# CameraTrigger.net
KiCad netlist of a schematic drawn in EAGLE
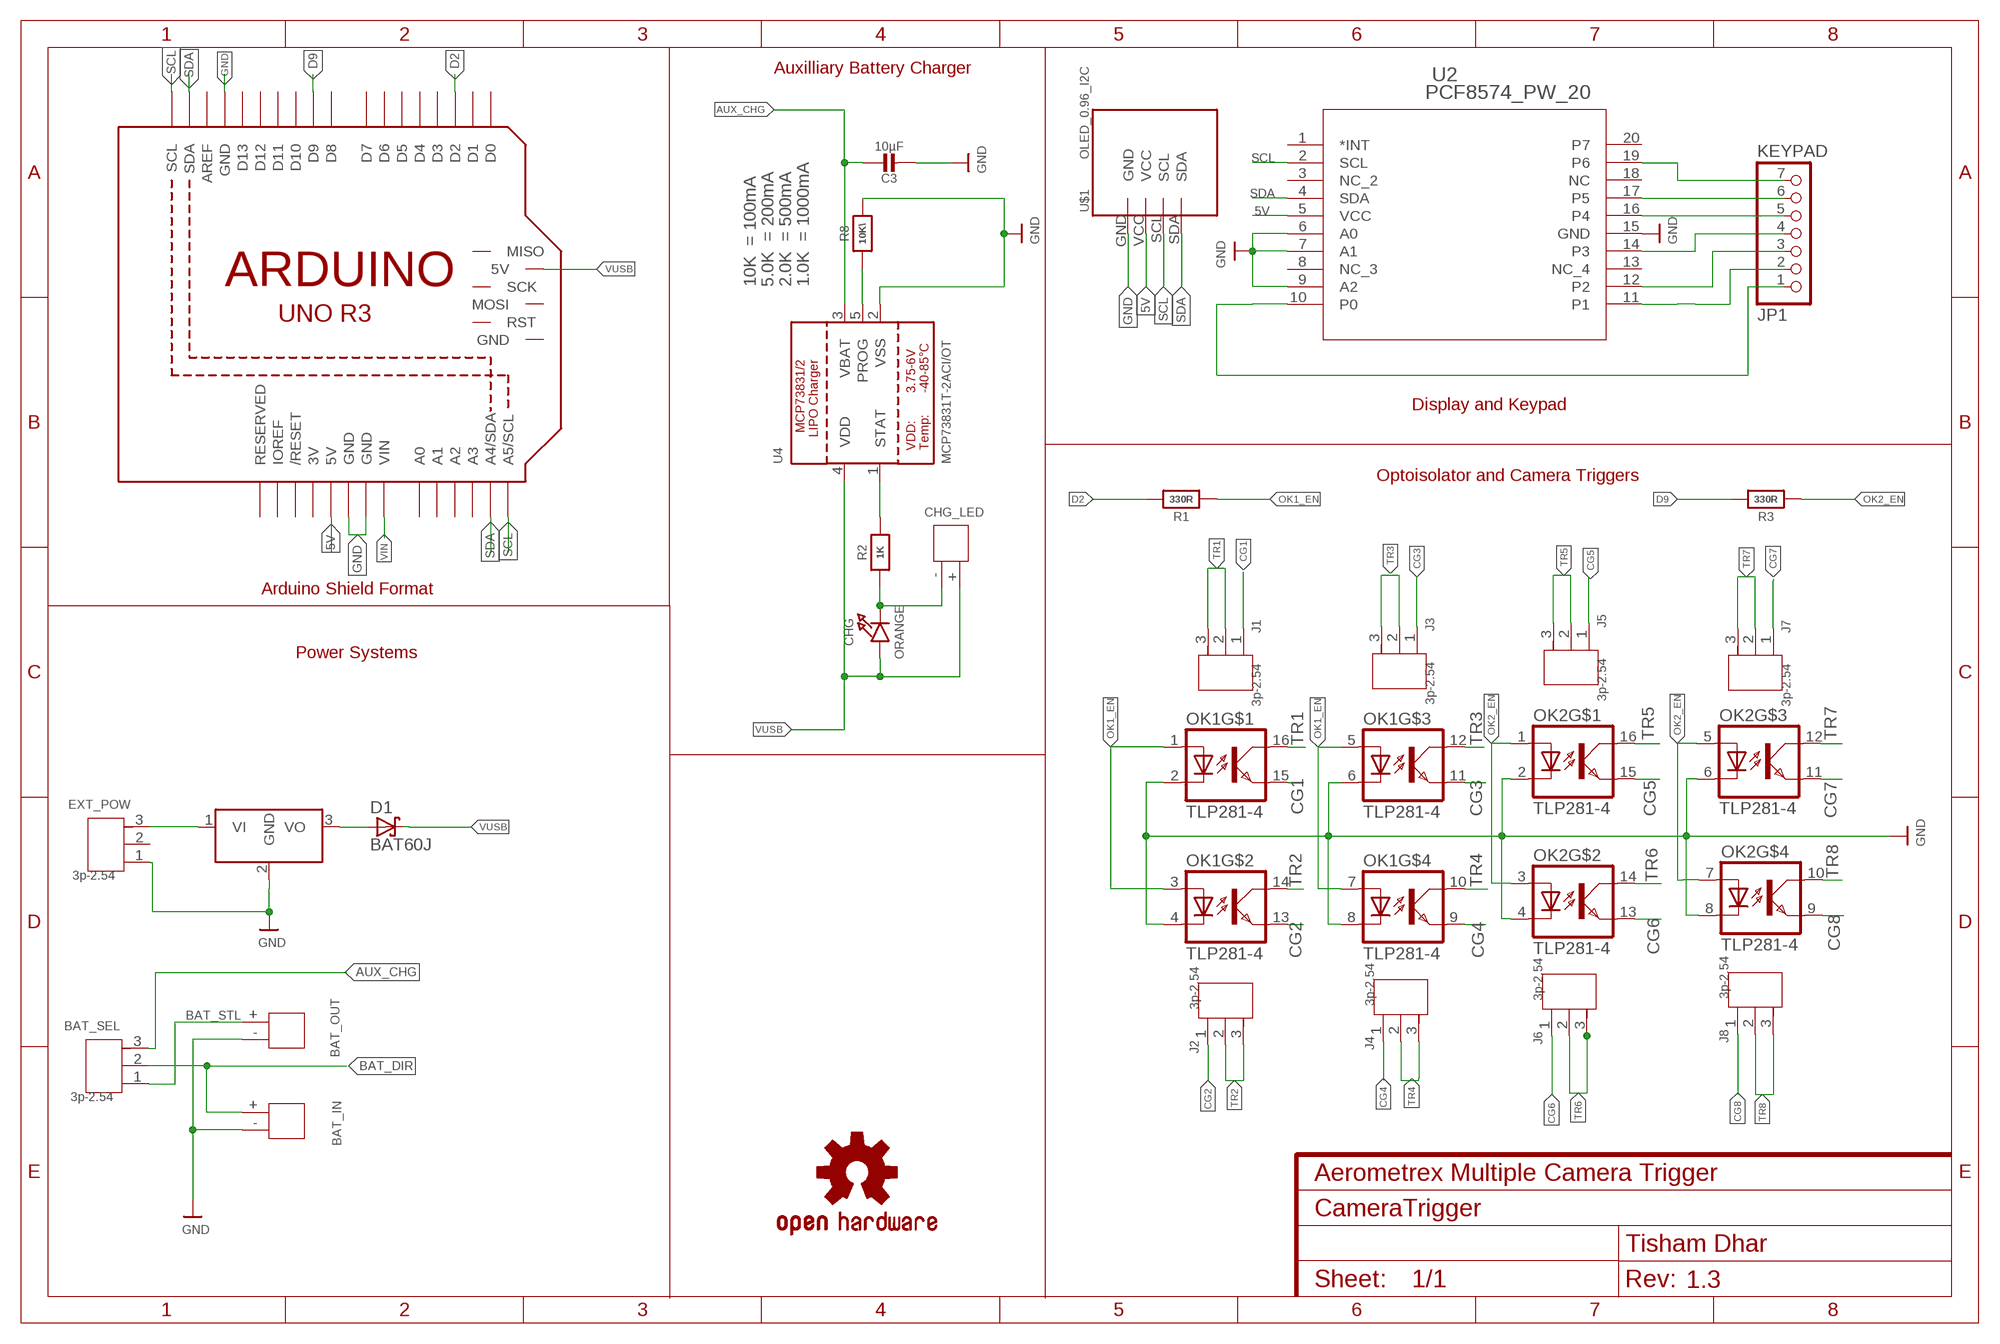
[diagram p0: schematic, sheet 1]

(export (version "E")
  (design (tool "Eeschema 10.0.6"))
  (components
    (comp (ref "BAT_IN")
      (value "2p-2.0")
      (footprint "eagle-import:H2-2.0-6X4.5MM")
      (libsource (lib "eagle-import") (part "DIP-JST-2P-2.0"))
    )
    (comp (ref "BAT_OUT")
      (value "2p-2.0")
      (footprint "eagle-import:H2-2.0-6X4.5MM")
      (libsource (lib "eagle-import") (part "DIP-JST-2P-2.0"))
    )
    (comp (ref "BAT_SEL")
      (value "3p-2.54")
      (footprint "eagle-import:HW3-2.54-7.62X6.6MM")
      (fields (field (name "MPN") "B101-103A0BSBA1"))
      (libsource (lib "eagle-import") (part "DIP-FEMALE-JST(3P-2.54)"))
    )
    (comp (ref "C3")
      (value "10µF")
      (footprint "eagle-import:0805-NO")
      (libsource (lib "eagle-import") (part "CAP_CERAMIC0805-NOOUTLINE"))
    )
    (comp (ref "CHG")
      (value "ORANGE")
      (footprint "eagle-import:CHIPLED_0805_NOOUTLINE")
      (libsource (lib "eagle-import") (part "LED0805_NOOUTLINE"))
    )
    (comp (ref "CHG_LED")
      (value "2p-2.0")
      (footprint "eagle-import:H2-2.0-6X4.5MM")
      (libsource (lib "eagle-import") (part "DIP-JST-2P-2.0"))
    )
    (comp (ref "D1")
      (value "BAT60J")
      (footprint "eagle-import:SOD323_ST")
      (libsource (lib "eagle-import") (part "BAT60J"))
    )
    (comp (ref "EXT_POW")
      (value "3p-2.54")
      (footprint "eagle-import:HW3-2.54-7.62X6.6MM")
      (fields (field (name "MPN") "B101-103A0BSBA1"))
      (libsource (lib "eagle-import") (part "DIP-FEMALE-JST(3P-2.54)"))
    )
    (comp (ref "J1")
      (value "3p-2.54")
      (footprint "eagle-import:HW3-2.54-7.62X6.6MM")
      (fields (field (name "MPN") "B101-103A0BSBA1"))
      (libsource (lib "eagle-import") (part "DIP-FEMALE-JST(3P-2.54)"))
    )
    (comp (ref "J2")
      (value "3p-2.54")
      (footprint "eagle-import:HW3-2.54-7.62X6.6MM")
      (fields (field (name "MPN") "B101-103A0BSBA1"))
      (libsource (lib "eagle-import") (part "DIP-FEMALE-JST(3P-2.54)"))
    )
    (comp (ref "J3")
      (value "3p-2.54")
      (footprint "eagle-import:HW3-2.54-7.62X6.6MM")
      (fields (field (name "MPN") "B101-103A0BSBA1"))
      (libsource (lib "eagle-import") (part "DIP-FEMALE-JST(3P-2.54)"))
    )
    (comp (ref "J4")
      (value "3p-2.54")
      (footprint "eagle-import:HW3-2.54-7.62X6.6MM")
      (fields (field (name "MPN") "B101-103A0BSBA1"))
      (libsource (lib "eagle-import") (part "DIP-FEMALE-JST(3P-2.54)"))
    )
    (comp (ref "J5")
      (value "3p-2.54")
      (footprint "eagle-import:HW3-2.54-7.62X6.6MM")
      (fields (field (name "MPN") "B101-103A0BSBA1"))
      (libsource (lib "eagle-import") (part "DIP-FEMALE-JST(3P-2.54)"))
    )
    (comp (ref "J6")
      (value "3p-2.54")
      (footprint "eagle-import:HW3-2.54-7.62X6.6MM")
      (fields (field (name "MPN") "B101-103A0BSBA1"))
      (libsource (lib "eagle-import") (part "DIP-FEMALE-JST(3P-2.54)"))
    )
    (comp (ref "J7")
      (value "3p-2.54")
      (footprint "eagle-import:HW3-2.54-7.62X6.6MM")
      (fields (field (name "MPN") "B101-103A0BSBA1"))
      (libsource (lib "eagle-import") (part "DIP-FEMALE-JST(3P-2.54)"))
    )
    (comp (ref "J8")
      (value "3p-2.54")
      (footprint "eagle-import:HW3-2.54-7.62X6.6MM")
      (fields (field (name "MPN") "B101-103A0BSBA1"))
      (libsource (lib "eagle-import") (part "DIP-FEMALE-JST(3P-2.54)"))
    )
    (comp (ref "JP1")
      (value "KEYPAD")
      (footprint "eagle-import:1X07")
      (libsource (lib "eagle-import") (part "PINHD-1X7"))
    )
    (comp (ref "LOGO1")
      (value "OSHW-LOGOM")
      (footprint "eagle-import:OSHW-LOGO-M")
      (libsource (lib "eagle-import") (part "OSHW-LOGOM"))
    )
    (comp (ref "M1")
      (value "ARDUINO_R3_ICSP")
      (footprint "eagle-import:ARDUINOR3_ICSP")
      (libsource (lib "eagle-import") (part "ARDUINO_R3_ICSP"))
    )
    (comp (ref "OK1")
      (value "TLP281-4")
      (footprint "eagle-import:MINI-FLAT-16")
      (libsource (lib "eagle-import") (part "TLP281-4"))
    )
    (comp (ref "OK2")
      (value "TLP281-4")
      (footprint "eagle-import:MINI-FLAT-16")
      (libsource (lib "eagle-import") (part "TLP281-4"))
    )
    (comp (ref "OKI-78SR-5")
      (value "DCDC_OKI-78SR")
      (footprint "eagle-import:OKI-78SRH")
      (libsource (lib "eagle-import") (part "DCDC_OKI-78SR"))
    )
    (comp (ref "R1")
      (value "330R")
      (footprint "eagle-import:0603-NO")
      (libsource (lib "eagle-import") (part "RESISTOR_0603_NOOUT"))
    )
    (comp (ref "R2")
      (value "1K")
      (footprint "eagle-import:0603-NO")
      (libsource (lib "eagle-import") (part "RESISTOR_0603_NOOUT"))
    )
    (comp (ref "R3")
      (value "330R")
      (footprint "eagle-import:0603-NO")
      (libsource (lib "eagle-import") (part "RESISTOR_0603_NOOUT"))
    )
    (comp (ref "R8")
      (value "10K\\")
      (footprint "eagle-import:0603-NO")
      (libsource (lib "eagle-import") (part "RESISTOR_0603_NOOUT"))
    )
    (comp (ref "U$1")
      (value "OLED_0.96_I2C")
      (footprint "eagle-import:OLED_0.96_I2C")
      (libsource (lib "eagle-import") (part "OLED_0.96_I2C"))
    )
    (comp (ref "U2")
      (value "PCF8574_PW_20")
      (footprint "eagle-import:PW20")
      (fields
        (field (name "GENERIC_PART_NUMBER") "PCF8574")
        (field (name "MANUFACTURER") "Texas Instruments")
        (field (name "MANUFACTURER_PART_NUMBER") "pcf8574_pw_20")
      )
      (libsource (lib "eagle-import") (part "PCF8574_PW_20"))
    )
    (comp (ref "U4")
      (value "MCP73831T-2ACI/OT")
      (footprint "eagle-import:SOT23-5")
      (libsource (lib "eagle-import") (part "MCP73831/2"))
    )
  )
  (nets
    (net (code "1") (name "/3V") (class "Default")
      (node (ref "M1") (pin "3V") (pinfunction "3V_3V") (pintype "power_in"))
    )
    (net (code "2") (name "/BAT_STL") (class "Default")
      (node (ref "BAT_OUT") (pin "+") (pinfunction "P$1_+") (pintype "bidirectional"))
      (node (ref "BAT_SEL") (pin "1") (pinfunction "P$1_1") (pintype "bidirectional"))
    )
    (net (code "3") (name "5V") (class "Default")
      (node (ref "M1") (pin "5V") (pinfunction "5V_5V") (pintype "power_in"))
      (node (ref "U$1") (pin "VCC") (pinfunction "VCC_VCC") (pintype "bidirectional"))
      (node (ref "U2") (pin "5") (pinfunction "VCC_5") (pintype "power_in"))
    )
    (net (code "4") (name "AUX_CHG") (class "Default")
      (node (ref "BAT_SEL") (pin "3") (pinfunction "P$3_3") (pintype "bidirectional"))
      (node (ref "C3") (pin "1") (pinfunction "1_1") (pintype "passive"))
      (node (ref "U4") (pin "3") (pinfunction "VBAT_3") (pintype "power_in"))
    )
    (net (code "5") (name "BAT_DIR") (class "Default")
      (node (ref "BAT_IN") (pin "+") (pinfunction "P$1_+") (pintype "bidirectional"))
      (node (ref "BAT_SEL") (pin "2") (pinfunction "P$2_2") (pintype "bidirectional"))
    )
    (net (code "6") (name "CG1") (class "Default")
      (node (ref "J1") (pin "1") (pinfunction "P$1_1") (pintype "bidirectional"))
      (node (ref "OK1") (pin "15") (pinfunction "EMIT_15") (pintype "passive"))
    )
    (net (code "7") (name "CG2") (class "Default")
      (node (ref "J2") (pin "1") (pinfunction "P$1_1") (pintype "bidirectional"))
      (node (ref "OK1") (pin "13") (pinfunction "EMIT_13") (pintype "passive"))
    )
    (net (code "8") (name "CG3") (class "Default")
      (node (ref "J3") (pin "1") (pinfunction "P$1_1") (pintype "bidirectional"))
      (node (ref "OK1") (pin "11") (pinfunction "EMIT_11") (pintype "passive"))
    )
    (net (code "9") (name "CG4") (class "Default")
      (node (ref "J4") (pin "1") (pinfunction "P$1_1") (pintype "bidirectional"))
      (node (ref "OK1") (pin "9") (pinfunction "EMIT_9") (pintype "passive"))
    )
    (net (code "10") (name "CG5") (class "Default")
      (node (ref "J5") (pin "1") (pinfunction "P$1_1") (pintype "bidirectional"))
      (node (ref "OK2") (pin "15") (pinfunction "EMIT_15") (pintype "passive"))
    )
    (net (code "11") (name "CG6") (class "Default")
      (node (ref "J6") (pin "1") (pinfunction "P$1_1") (pintype "bidirectional"))
      (node (ref "OK2") (pin "13") (pinfunction "EMIT_13") (pintype "passive"))
    )
    (net (code "12") (name "CG7") (class "Default")
      (node (ref "J7") (pin "1") (pinfunction "P$1_1") (pintype "bidirectional"))
      (node (ref "OK2") (pin "11") (pinfunction "EMIT_11") (pintype "passive"))
    )
    (net (code "13") (name "CG8") (class "Default")
      (node (ref "J8") (pin "1") (pinfunction "P$1_1") (pintype "bidirectional"))
      (node (ref "OK2") (pin "9") (pinfunction "EMIT_9") (pintype "passive"))
    )
    (net (code "14") (name "D2") (class "Default")
      (node (ref "M1") (pin "D2") (pinfunction "D2_D2") (pintype "bidirectional"))
      (node (ref "R1") (pin "2") (pinfunction "2_2") (pintype "passive"))
    )
    (net (code "15") (name "D9") (class "Default")
      (node (ref "M1") (pin "D9") (pinfunction "D9_D9") (pintype "bidirectional"))
      (node (ref "R3") (pin "2") (pinfunction "2_2") (pintype "passive"))
    )
    (net (code "16") (name "GND") (class "Default")
      (node (ref "BAT_IN") (pin "-") (pinfunction "P$2_-") (pintype "bidirectional"))
      (node (ref "BAT_OUT") (pin "-") (pinfunction "P$2_-") (pintype "bidirectional"))
      (node (ref "C3") (pin "2") (pinfunction "2_2") (pintype "passive"))
      (node (ref "EXT_POW") (pin "1") (pinfunction "P$1_1") (pintype "bidirectional"))
      (node (ref "M1") (pin "GND") (pinfunction "GND_GND") (pintype "power_in"))
      (node (ref "M1") (pin "GND@1") (pinfunction "GND_GND@1") (pintype "power_in"))
      (node (ref "M1") (pin "GND@3") (pinfunction "GND_GND@3") (pintype "power_in"))
      (node (ref "OK1") (pin "2") (pinfunction "C_2") (pintype "passive"))
      (node (ref "OK1") (pin "4") (pinfunction "C_4") (pintype "passive"))
      (node (ref "OK1") (pin "6") (pinfunction "C_6") (pintype "passive"))
      (node (ref "OK1") (pin "8") (pinfunction "C_8") (pintype "passive"))
      (node (ref "OK2") (pin "2") (pinfunction "C_2") (pintype "passive"))
      (node (ref "OK2") (pin "4") (pinfunction "C_4") (pintype "passive"))
      (node (ref "OK2") (pin "6") (pinfunction "C_6") (pintype "passive"))
      (node (ref "OK2") (pin "8") (pinfunction "C_8") (pintype "passive"))
      (node (ref "OKI-78SR-5") (pin "2") (pinfunction "GND_2") (pintype "bidirectional"))
      (node (ref "R8") (pin "2") (pinfunction "2_2") (pintype "passive"))
      (node (ref "U$1") (pin "GND") (pinfunction "GND_GND") (pintype "bidirectional"))
      (node (ref "U2") (pin "15") (pinfunction "GND_15") (pintype "power_in"))
      (node (ref "U2") (pin "6") (pinfunction "A0_6") (pintype "input"))
      (node (ref "U2") (pin "7") (pinfunction "A1_7") (pintype "input"))
      (node (ref "U2") (pin "9") (pinfunction "A2_9") (pintype "input"))
      (node (ref "U4") (pin "2") (pinfunction "VSS_2") (pintype "power_in"))
    )
    (net (code "17") (name "Net-(CHG_LED-P$2)") (class "Default")
      (node (ref "CHG") (pin "C") (pinfunction "C_C") (pintype "passive"))
      (node (ref "CHG_LED") (pin "-") (pinfunction "P$2_-") (pintype "bidirectional"))
      (node (ref "R2") (pin "1") (pinfunction "1_1") (pintype "passive"))
    )
    (net (code "18") (name "Net-(EXT_POW-P$3)") (class "Default")
      (node (ref "EXT_POW") (pin "3") (pinfunction "P$3_3") (pintype "bidirectional"))
      (node (ref "OKI-78SR-5") (pin "1") (pinfunction "VI_1") (pintype "bidirectional"))
    )
    (net (code "19") (name "Net-(OKI-78SR-5-VO)") (class "Default")
      (node (ref "D1") (pin "A") (pinfunction "A_A") (pintype "passive"))
      (node (ref "OKI-78SR-5") (pin "3") (pinfunction "VO_3") (pintype "bidirectional"))
    )
    (net (code "20") (name "Net-(U2-P0)") (class "Default")
      (node (ref "JP1") (pin "1") (pinfunction "1_1") (pintype "passive"))
      (node (ref "U2") (pin "10") (pinfunction "P0_10") (pintype "bidirectional"))
    )
    (net (code "21") (name "Net-(U2-P1)") (class "Default")
      (node (ref "JP1") (pin "2") (pinfunction "2_2") (pintype "passive"))
      (node (ref "U2") (pin "11") (pinfunction "P1_11") (pintype "bidirectional"))
    )
    (net (code "22") (name "Net-(U2-P2)") (class "Default")
      (node (ref "JP1") (pin "3") (pinfunction "3_3") (pintype "passive"))
      (node (ref "U2") (pin "12") (pinfunction "P2_12") (pintype "bidirectional"))
    )
    (net (code "23") (name "Net-(U2-P3)") (class "Default")
      (node (ref "JP1") (pin "4") (pinfunction "4_4") (pintype "passive"))
      (node (ref "U2") (pin "14") (pinfunction "P3_14") (pintype "bidirectional"))
    )
    (net (code "24") (name "Net-(U2-P4)") (class "Default")
      (node (ref "JP1") (pin "5") (pinfunction "5_5") (pintype "passive"))
      (node (ref "U2") (pin "16") (pinfunction "P4_16") (pintype "bidirectional"))
    )
    (net (code "25") (name "Net-(U2-P5)") (class "Default")
      (node (ref "JP1") (pin "6") (pinfunction "6_6") (pintype "passive"))
      (node (ref "U2") (pin "17") (pinfunction "P5_17") (pintype "bidirectional"))
    )
    (net (code "26") (name "Net-(U2-P6)") (class "Default")
      (node (ref "JP1") (pin "7") (pinfunction "7_7") (pintype "passive"))
      (node (ref "U2") (pin "19") (pinfunction "P6_19") (pintype "bidirectional"))
    )
    (net (code "27") (name "Net-(U4-PROG)") (class "Default")
      (node (ref "R8") (pin "1") (pinfunction "1_1") (pintype "passive"))
      (node (ref "U4") (pin "5") (pinfunction "PROG_5") (pintype "input"))
    )
    (net (code "28") (name "Net-(U4-STAT)") (class "Default")
      (node (ref "R2") (pin "2") (pinfunction "2_2") (pintype "passive"))
      (node (ref "U4") (pin "1") (pinfunction "STAT_1") (pintype "output"))
    )
    (net (code "29") (name "OK1_EN") (class "Default")
      (node (ref "OK1") (pin "1") (pinfunction "A_1") (pintype "passive"))
      (node (ref "OK1") (pin "3") (pinfunction "A_3") (pintype "passive"))
      (node (ref "OK1") (pin "5") (pinfunction "A_5") (pintype "passive"))
      (node (ref "OK1") (pin "7") (pinfunction "A_7") (pintype "passive"))
      (node (ref "R1") (pin "1") (pinfunction "1_1") (pintype "passive"))
    )
    (net (code "30") (name "OK2_EN") (class "Default")
      (node (ref "OK2") (pin "1") (pinfunction "A_1") (pintype "passive"))
      (node (ref "OK2") (pin "3") (pinfunction "A_3") (pintype "passive"))
      (node (ref "OK2") (pin "5") (pinfunction "A_5") (pintype "passive"))
      (node (ref "OK2") (pin "7") (pinfunction "A_7") (pintype "passive"))
      (node (ref "R3") (pin "1") (pinfunction "1_1") (pintype "passive"))
    )
    (net (code "31") (name "SCL") (class "Default")
      (node (ref "M1") (pin "A5") (pinfunction "A5/SCL_A5") (pintype "bidirectional"))
      (node (ref "M1") (pin "SCL") (pinfunction "SCL_SCL") (pintype "bidirectional"))
      (node (ref "U$1") (pin "SCL") (pinfunction "SCL_SCL") (pintype "bidirectional"))
      (node (ref "U2") (pin "2") (pinfunction "SCL_2") (pintype "passive"))
    )
    (net (code "32") (name "SDA") (class "Default")
      (node (ref "M1") (pin "A4") (pinfunction "A4/SDA_A4") (pintype "bidirectional"))
      (node (ref "M1") (pin "SDA") (pinfunction "SDA_SDA") (pintype "bidirectional"))
      (node (ref "U$1") (pin "SDA") (pinfunction "SDA_SDA") (pintype "bidirectional"))
      (node (ref "U2") (pin "4") (pinfunction "SDA_4") (pintype "passive"))
    )
    (net (code "33") (name "TR1") (class "Default")
      (node (ref "J1") (pin "2") (pinfunction "P$2_2") (pintype "bidirectional"))
      (node (ref "J1") (pin "3") (pinfunction "P$3_3") (pintype "bidirectional"))
      (node (ref "OK1") (pin "16") (pinfunction "COL_16") (pintype "passive"))
    )
    (net (code "34") (name "TR2") (class "Default")
      (node (ref "J2") (pin "2") (pinfunction "P$2_2") (pintype "bidirectional"))
      (node (ref "J2") (pin "3") (pinfunction "P$3_3") (pintype "bidirectional"))
      (node (ref "OK1") (pin "14") (pinfunction "COL_14") (pintype "passive"))
    )
    (net (code "35") (name "TR3") (class "Default")
      (node (ref "J3") (pin "2") (pinfunction "P$2_2") (pintype "bidirectional"))
      (node (ref "J3") (pin "3") (pinfunction "P$3_3") (pintype "bidirectional"))
      (node (ref "OK1") (pin "12") (pinfunction "COL_12") (pintype "passive"))
    )
    (net (code "36") (name "TR4") (class "Default")
      (node (ref "J4") (pin "2") (pinfunction "P$2_2") (pintype "bidirectional"))
      (node (ref "J4") (pin "3") (pinfunction "P$3_3") (pintype "bidirectional"))
      (node (ref "OK1") (pin "10") (pinfunction "COL_10") (pintype "passive"))
    )
    (net (code "37") (name "TR5") (class "Default")
      (node (ref "J5") (pin "2") (pinfunction "P$2_2") (pintype "bidirectional"))
      (node (ref "J5") (pin "3") (pinfunction "P$3_3") (pintype "bidirectional"))
      (node (ref "OK2") (pin "16") (pinfunction "COL_16") (pintype "passive"))
    )
    (net (code "38") (name "TR6") (class "Default")
      (node (ref "J6") (pin "2") (pinfunction "P$2_2") (pintype "bidirectional"))
      (node (ref "J6") (pin "3") (pinfunction "P$3_3") (pintype "bidirectional"))
      (node (ref "OK2") (pin "14") (pinfunction "COL_14") (pintype "passive"))
    )
    (net (code "39") (name "TR7") (class "Default")
      (node (ref "J7") (pin "2") (pinfunction "P$2_2") (pintype "bidirectional"))
      (node (ref "J7") (pin "3") (pinfunction "P$3_3") (pintype "bidirectional"))
      (node (ref "OK2") (pin "12") (pinfunction "COL_12") (pintype "passive"))
    )
    (net (code "40") (name "TR8") (class "Default")
      (node (ref "J8") (pin "2") (pinfunction "P$2_2") (pintype "bidirectional"))
      (node (ref "J8") (pin "3") (pinfunction "P$3_3") (pintype "bidirectional"))
      (node (ref "OK2") (pin "10") (pinfunction "COL_10") (pintype "passive"))
    )
    (net (code "41") (name "VIN") (class "Default")
      (node (ref "M1") (pin "VIN") (pinfunction "VIN_VIN") (pintype "power_in"))
    )
    (net (code "42") (name "VUSB") (class "Default")
      (node (ref "CHG") (pin "A") (pinfunction "A_A") (pintype "passive"))
      (node (ref "CHG_LED") (pin "+") (pinfunction "P$1_+") (pintype "bidirectional"))
      (node (ref "D1") (pin "C") (pinfunction "C_C") (pintype "passive"))
      (node (ref "M1") (pin "5V_ICSP") (pinfunction "5V_5V_ICSP") (pintype "passive"))
      (node (ref "U4") (pin "4") (pinfunction "VDD_4") (pintype "power_in"))
    )
    (net (code "43") (name "unconnected-(EXT_POW-P$2-Pad2)") (class "Default")
      (node (ref "EXT_POW") (pin "2") (pinfunction "P$2_2") (pintype "bidirectional"))
    )
    (net (code "44") (name "unconnected-(M1-GND-PadGND@2)") (class "Default")
      (node (ref "M1") (pin "GND@2") (pinfunction "GND_GND@2") (pintype "passive"))
    )
    (net (code "45") (name "unconnected-(M1-PadA0)") (class "Default")
      (node (ref "M1") (pin "A0") (pinfunction "A0_A0") (pintype "bidirectional"))
    )
    (net (code "46") (name "unconnected-(M1-PadA1)") (class "Default")
      (node (ref "M1") (pin "A1") (pinfunction "A1_A1") (pintype "bidirectional"))
    )
    (net (code "47") (name "unconnected-(M1-PadA2)") (class "Default")
      (node (ref "M1") (pin "A2") (pinfunction "A2_A2") (pintype "bidirectional"))
    )
    (net (code "48") (name "unconnected-(M1-PadA3)") (class "Default")
      (node (ref "M1") (pin "A3") (pinfunction "A3_A3") (pintype "bidirectional"))
    )
    (net (code "49") (name "unconnected-(M1-PadAREF)") (class "Default")
      (node (ref "M1") (pin "AREF") (pinfunction "AREF_AREF") (pintype "bidirectional"))
    )
    (net (code "50") (name "unconnected-(M1-PadD0)") (class "Default")
      (node (ref "M1") (pin "D0") (pinfunction "D0_D0") (pintype "bidirectional"))
    )
    (net (code "51") (name "unconnected-(M1-PadD1)") (class "Default")
      (node (ref "M1") (pin "D1") (pinfunction "D1_D1") (pintype "bidirectional"))
    )
    (net (code "52") (name "unconnected-(M1-PadD3)") (class "Default")
      (node (ref "M1") (pin "D3") (pinfunction "D3_D3") (pintype "bidirectional"))
    )
    (net (code "53") (name "unconnected-(M1-PadD4)") (class "Default")
      (node (ref "M1") (pin "D4") (pinfunction "D4_D4") (pintype "bidirectional"))
    )
    (net (code "54") (name "unconnected-(M1-PadD5)") (class "Default")
      (node (ref "M1") (pin "D5") (pinfunction "D5_D5") (pintype "bidirectional"))
    )
    (net (code "55") (name "unconnected-(M1-PadD6)") (class "Default")
      (node (ref "M1") (pin "D6") (pinfunction "D6_D6") (pintype "bidirectional"))
    )
    (net (code "56") (name "unconnected-(M1-PadD7)") (class "Default")
      (node (ref "M1") (pin "D7") (pinfunction "D7_D7") (pintype "bidirectional"))
    )
    (net (code "57") (name "unconnected-(M1-PadD8)") (class "Default")
      (node (ref "M1") (pin "D8") (pinfunction "D8_D8") (pintype "bidirectional"))
    )
    (net (code "58") (name "unconnected-(M1-PadD10)") (class "Default")
      (node (ref "M1") (pin "D10") (pinfunction "D10_D10") (pintype "bidirectional"))
    )
    (net (code "59") (name "unconnected-(M1-PadD11)") (class "Default")
      (node (ref "M1") (pin "D11") (pinfunction "D11_D11") (pintype "bidirectional"))
    )
    (net (code "60") (name "unconnected-(M1-PadD12)") (class "Default")
      (node (ref "M1") (pin "D12") (pinfunction "D12_D12") (pintype "bidirectional"))
    )
    (net (code "61") (name "unconnected-(M1-PadD13)") (class "Default")
      (node (ref "M1") (pin "D13") (pinfunction "D13_D13") (pintype "bidirectional"))
    )
    (net (code "62") (name "unconnected-(M1-PadIOREF)") (class "Default")
      (node (ref "M1") (pin "IOREF") (pinfunction "IOREF_IOREF") (pintype "output"))
    )
    (net (code "63") (name "unconnected-(M1-PadMISO)") (class "Default")
      (node (ref "M1") (pin "MISO") (pinfunction "MISO_MISO") (pintype "passive"))
    )
    (net (code "64") (name "unconnected-(M1-PadMOSI)") (class "Default")
      (node (ref "M1") (pin "MOSI") (pinfunction "MOSI_MOSI") (pintype "passive"))
    )
    (net (code "65") (name "unconnected-(M1-PadRESERVED)") (class "Default")
      (node (ref "M1") (pin "RESERVED") (pinfunction "RESERVED_RESERVED") (pintype "no_connect"))
    )
    (net (code "66") (name "unconnected-(M1-PadSCK)") (class "Default")
      (node (ref "M1") (pin "SCK") (pinfunction "SCK_SCK") (pintype "passive"))
    )
    (net (code "67") (name "unconnected-(M1-RST-PadRESET_ICSP)") (class "Default")
      (node (ref "M1") (pin "RESET_ICSP") (pinfunction "RST_RESET_ICSP") (pintype "passive"))
    )
    (net (code "68") (name "unconnected-(M1-{slash}RESET-PadRESET)") (class "Default")
      (node (ref "M1") (pin "RESET") (pinfunction "/RESET_RESET") (pintype "bidirectional"))
    )
    (net (code "69") (name "unconnected-(U2-*INT-Pad1)") (class "Default")
      (node (ref "U2") (pin "1") (pinfunction "*INT_1") (pintype "output"))
    )
    (net (code "70") (name "unconnected-(U2-NC-Pad18)") (class "Default")
      (node (ref "U2") (pin "18") (pinfunction "NC_18") (pintype "passive"))
    )
    (net (code "71") (name "unconnected-(U2-NC_2-Pad3)") (class "Default")
      (node (ref "U2") (pin "3") (pinfunction "NC_2_3") (pintype "passive"))
    )
    (net (code "72") (name "unconnected-(U2-NC_3-Pad8)") (class "Default")
      (node (ref "U2") (pin "8") (pinfunction "NC_3_8") (pintype "passive"))
    )
    (net (code "73") (name "unconnected-(U2-NC_4-Pad13)") (class "Default")
      (node (ref "U2") (pin "13") (pinfunction "NC_4_13") (pintype "passive"))
    )
    (net (code "74") (name "unconnected-(U2-P7-Pad20)") (class "Default")
      (node (ref "U2") (pin "20") (pinfunction "P7_20") (pintype "bidirectional"))
    )
  )
)
